# TMC2590_BOB40_V1_0.net
KiCad netlist of a schematic drawn in Altium Designer
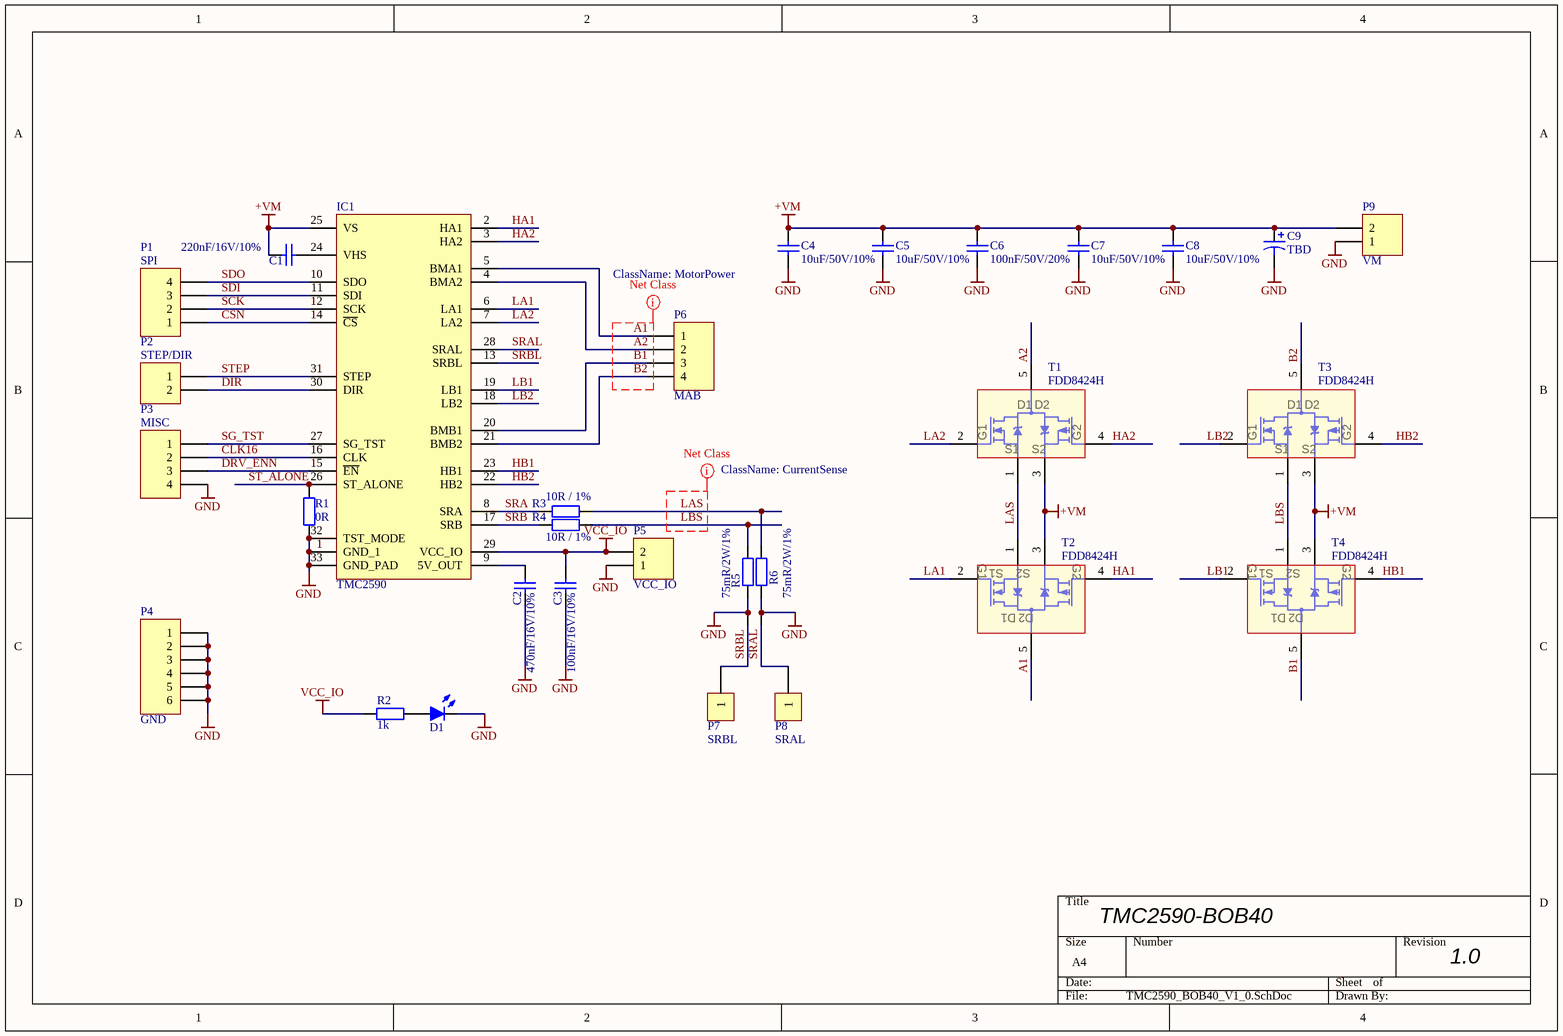
[diagram p0: TMC2590_BOB40_V1_0.SchDoc]

(export (version "E")
  (design (tool "Eeschema 10.0.6"))
  (components
    (comp (ref "C1")
      (value "220nF/16V/10%")
      (footprint "C0603")
      (description "Ceramic capacitor")
      (fields (field (name "MF") "Multicomp") (field (name "MPN") "MC0603B224K160CT"))
      (libsource (lib "SCH Passives") (part "Capacitor"))
    )
    (comp (ref "C2")
      (value "470nF/16V/10%")
      (footprint "C0603")
      (description "Ceramic capacitor")
      (fields (field (name "MF") "Multicomp") (field (name "MPN") "MC0603X474K160CT"))
      (libsource (lib "SCH Passives") (part "Capacitor"))
    )
    (comp (ref "C3")
      (value "100nF/16V/10%")
      (footprint "C0603")
      (description "Ceramic capacitor")
      (fields (field (name "MF") "Multicomp") (field (name "MPN") "MC0603B104K160CT"))
      (libsource (lib "SCH Passives") (part "Capacitor"))
    )
    (comp (ref "C4")
      (value "10uF/50V/10%")
      (footprint "C1206")
      (description "SMD Multilayer Ceramic Capacitor, 1206 [3216 Metric],10 µF, 50 V, ± 10%, X5R, GRM Series")
      (fields (field (name "MF") "MURATA") (field (name "MPN") "GRM31CR61H106KA12L"))
      (libsource (lib "TMC260_BOB_V1_1") (part "10 µF, 50 V, ± 10%, X5R, 1206 [3216 Metric]"))
    )
    (comp (ref "C5")
      (value "10uF/50V/10%")
      (footprint "C1206")
      (description "SMD Multilayer Ceramic Capacitor, 1206 [3216 Metric],10 µF, 50 V, ± 10%, X5R, GRM Series")
      (fields (field (name "MF") "MURATA") (field (name "MPN") "GRM31CR61H106KA12L"))
      (libsource (lib "TMC260_BOB_V1_1") (part "10 µF, 50 V, ± 10%, X5R, 1206 [3216 Metric]"))
    )
    (comp (ref "C6")
      (value "100nF/50V/20%")
      (footprint "C0603")
      (description "Ceramic capacitor")
      (fields (field (name "MF") "Multicomp") (field (name "MPN") "MC0603F104M500CT"))
      (libsource (lib "SCH Passives") (part "Capacitor"))
    )
    (comp (ref "C7")
      (value "10uF/50V/10%")
      (footprint "C1206")
      (description "SMD Multilayer Ceramic Capacitor, 1206 [3216 Metric],10 µF, 50 V, ± 10%, X5R, GRM Series")
      (fields (field (name "MF") "MURATA") (field (name "MPN") "GRM31CR61H106KA12L"))
      (libsource (lib "TMC260_BOB_V1_1") (part "10 µF, 50 V, ± 10%, X5R, 1206 [3216 Metric]"))
    )
    (comp (ref "C8")
      (value "10uF/50V/10%")
      (footprint "C1206")
      (description "SMD Multilayer Ceramic Capacitor, 1206 [3216 Metric],10 µF, 50 V, ± 10%, X5R, GRM Series")
      (fields (field (name "MF") "MURATA") (field (name "MPN") "GRM31CR61H106KA12L"))
      (libsource (lib "TMC260_BOB_V1_1") (part "10 µF, 50 V, ± 10%, X5R, 1206 [3216 Metric]"))
    )
    (comp (ref "C9")
      (value "TBD")
      (footprint "EXT_POL_CAP")
      (description "Polarized Capacitor (Radial)")
      (fields (field (name "Comment") "Cap Pol1") (field (name "PUBLISHER") "Altium Limited"))
      (libsource (lib "Miscellaneous Devices") (part "Cap Pol1"))
    )
    (comp (ref "D1")
      (value "LED, Blue, SMD, 20mA, 2.8V, 465 nm")
      (footprint "LED_0603")
      (fields (field (name "MF") "Lite-On") (field (name "MPN") "LTST-C191TBKT-5A"))
      (libsource (lib "TMC26x_RevA") (part "LED, Blue, SMD, 20mA, 2.8V, 465 nm"))
    )
    (comp (ref "IC1")
      (value "TMC2590")
      (footprint "TMC2590_QFP127P600-8N")
      (fields (field (name "MF") "TRINAMIC"))
      (libsource (lib "TMC2590_BOB40_V1_0") (part "TMC2590"))
    )
    (comp (ref "J1")
      (value "Net tie")
      (footprint "Net tie 10x20mil")
      (libsource (lib "TMC2590_BOB40_V1_0") (part "NET_TIE"))
    )
    (comp (ref "J2")
      (value "Net tie")
      (footprint "Net tie 10x20mil")
      (libsource (lib "TMC2590_BOB40_V1_0") (part "NET_TIE"))
    )
    (comp (ref "P1")
      (value "SPI")
      (footprint "4_PIN_THT")
      (description "Header, 4-Pin")
      (fields (field (name "PUBLISHER") "Altium Limited"))
      (libsource (lib "Miscellaneous Connectors") (part "Header 4"))
    )
    (comp (ref "P2")
      (value "STEP/DIR")
      (footprint "2_PIN_THT")
      (description "Header, 2-Pin")
      (fields (field (name "PUBLISHER") "Altium Limited"))
      (libsource (lib "") (part "Header 2_1"))
    )
    (comp (ref "P3")
      (value "MISC")
      (footprint "4_PIN_THT")
      (description "Header, 4-Pin")
      (fields (field (name "PUBLISHER") "Altium Limited"))
      (libsource (lib "") (part "Header 4_1"))
    )
    (comp (ref "P4")
      (value "GND")
      (footprint "6_PIN_THT")
      (description "Header, 6-Pin")
      (fields (field (name "PUBLISHER") "Altium Limited"))
      (libsource (lib "Miscellaneous Connectors") (part "Header 6"))
    )
    (comp (ref "P5")
      (value "VCC_IO")
      (footprint "2_PIN_THT")
      (description "Header, 2-Pin")
      (fields (field (name "PUBLISHER") "Altium Limited"))
      (libsource (lib "Miscellaneous Connectors") (part "Header 2"))
    )
    (comp (ref "P6")
      (value "MAB")
      (footprint "4_PIN_THT_1mm_hole")
      (description "Wire-To-Board Connector, 2.5 mm, 4 Contacts, Header, EH Series, Through Hole, 1 Rows")
      (fields (field (name "MPN") "B4B-EH-A") (field (name "MF") "JST (JAPAN SOLDERLESS TERMINALS)"))
      (libsource (lib "TMC5160_RevA") (part "Wire-To-Board Connector, 2.5 mm, 4 Contacts, Header, EH Series, Through Hole, 1 Rows"))
    )
    (comp (ref "P7")
      (value "SRBL")
      (footprint "TH_PIN - NO SILK")
      (libsource (lib "StepperMotorDriver_revA") (part "PIN"))
    )
    (comp (ref "P8")
      (value "SRAL")
      (footprint "TH_PIN - NO SILK")
      (libsource (lib "StepperMotorDriver_revA") (part "PIN"))
    )
    (comp (ref "P9")
      (value "VM")
      (footprint "2_PIN_THT")
      (description "Header, 2-Pin")
      (fields (field (name "PUBLISHER") "Altium Limited"))
      (libsource (lib "Miscellaneous Connectors") (part "Header 2"))
    )
    (comp (ref "R1")
      (value "0R")
      (footprint "R0603")
      (description "SMD Chip Resistor, Thick Film, 0 ohm, 0603 [1608 Metric], 100 mW, MCWR Series")
      (fields
        (field (name "MPN") "MCWR06X000 PTL")
        (field (name "MF") "MULTICOMP")
        (field (name "RESISTANCE") "0R")
      )
      (libsource (lib "SMD_Passives") (part "R, 0 ohm, 0603 [1608 Metric], 100 mW, MCWR Series"))
    )
    (comp (ref "R2")
      (value "1k")
      (footprint "R0603")
      (description "1 kohm, 50 V, 0603 [1608 Metric], 63 mW, ± 1%, MC Series")
      (fields
        (field (name "MPN") "MC0063W060311K")
        (field (name "MF") "MULTICOMP")
        (field (name "RESISTANCE") "1k")
      )
      (libsource (lib "TMC457_RevA") (part "1 kohm, 50 V, 0603 [1608 Metric], 63 mW, ± 1%, MC Series"))
    )
    (comp (ref "R3")
      (value "10R / 1%")
      (footprint "R0603")
      (description "SMD Chip Resistor, Thick Film, 10 ohm, 50 V, 0603 [1608 Metric], 100 mW, ± 1%, MCWR Series")
      (fields (field (name "MPN") "MCWR06X10R0FTL") (field (name "MF") "Multicomp"))
      (libsource (lib "TMC262_RevA") (part ".05 OHM 2W 1% Current Sense Resistor"))
    )
    (comp (ref "R4")
      (value "10R / 1%")
      (footprint "R0603")
      (description "SMD Chip Resistor, Thick Film, 10 ohm, 50 V, 0603 [1608 Metric], 100 mW, ± 1%, MCWR Series")
      (fields (field (name "MPN") "MCWR06X10R0FTL") (field (name "MF") "Multicomp"))
      (libsource (lib "TMC262_RevA") (part ".05 OHM 2W 1% Current Sense Resistor"))
    )
    (comp (ref "R5")
      (value "75mR/2W/1%")
      (footprint "R2512")
      (description "SMD Current Sense Resistor, 0.075 ohm, 2 W, 2512 [6432 Metric], ± 1%, TLR Series")
      (fields (field (name "MPN") "TLR3A20WR075FTDG") (field (name "MF") "TE CONNECTIVITY"))
      (libsource (lib "TMC262_RevA") (part ".075 OHM 2W 1% Current Sense Resistor"))
    )
    (comp (ref "R6")
      (value "75mR/2W/1%")
      (footprint "R2512")
      (description "SMD Current Sense Resistor, 0.075 ohm, 2 W, 2512 [6432 Metric], ± 1%, TLR Series")
      (fields (field (name "MPN") "TLR3A20WR075FTDG") (field (name "MF") "TE CONNECTIVITY"))
      (libsource (lib "TMC262_RevA") (part ".075 OHM 2W 1% Current Sense Resistor"))
    )
    (comp (ref "T1")
      (value "FDD8424H")
      (footprint "SOT114P991X239-6N")
      (description "Dual MOSFET, N and P Channel, 9 A, 40 V, 0.019 ohm, 10 V, 1.7 V")
      (fields (field (name "MF") "FAIRCHILD SEMICONDUCTOR"))
      (libsource (lib "") (part "FDD8424H_1"))
    )
    (comp (ref "T2")
      (value "FDD8424H")
      (footprint "SOT114P991X239-6N")
      (description "Dual MOSFET, N and P Channel, 9 A, 40 V, 0.019 ohm, 10 V, 1.7 V")
      (fields (field (name "MF") "FAIRCHILD SEMICONDUCTOR"))
      (libsource (lib "TMC262_FDD8424H_RevA") (part "FDD8424H"))
    )
    (comp (ref "T3")
      (value "FDD8424H")
      (footprint "SOT114P991X239-6N")
      (description "Dual MOSFET, N and P Channel, 9 A, 40 V, 0.019 ohm, 10 V, 1.7 V")
      (fields (field (name "MF") "FAIRCHILD SEMICONDUCTOR"))
      (libsource (lib "") (part "FDD8424H_1"))
    )
    (comp (ref "T4")
      (value "FDD8424H")
      (footprint "SOT114P991X239-6N")
      (description "Dual MOSFET, N and P Channel, 9 A, 40 V, 0.019 ohm, 10 V, 1.7 V")
      (fields (field (name "MF") "FAIRCHILD SEMICONDUCTOR"))
      (libsource (lib "TMC262_FDD8424H_RevA") (part "FDD8424H"))
    )
  )
  (nets
    (net (code "1") (name "+VM") (class "Default")
      (node (ref "C1") (pin "2") (pinfunction "2_2") (pintype "passive"))
      (node (ref "C4") (pin "2") (pinfunction "2_2") (pintype "passive"))
      (node (ref "C5") (pin "2") (pinfunction "2_2") (pintype "passive"))
      (node (ref "C6") (pin "2") (pinfunction "2_2") (pintype "passive"))
      (node (ref "C7") (pin "2") (pinfunction "2_2") (pintype "passive"))
      (node (ref "C8") (pin "2") (pinfunction "2_2") (pintype "passive"))
      (node (ref "C9") (pin "1") (pinfunction "1_1") (pintype "passive"))
      (node (ref "IC1") (pin "25") (pinfunction "VS_25") (pintype "power_in"))
      (node (ref "P9") (pin "2") (pinfunction "2_2") (pintype "passive"))
      (node (ref "T1") (pin "3") (pinfunction "S2_3") (pintype "passive"))
      (node (ref "T2") (pin "3") (pinfunction "S2_3") (pintype "passive"))
      (node (ref "T3") (pin "3") (pinfunction "S2_3") (pintype "passive"))
      (node (ref "T4") (pin "3") (pinfunction "S2_3") (pintype "passive"))
    )
    (net (code "2") (name "/A1") (class "Default")
      (node (ref "IC1") (pin "5") (pinfunction "BMA1_5") (pintype "passive"))
      (node (ref "P6") (pin "1") (pinfunction "1_1") (pintype "passive"))
      (node (ref "T2") (pin "5") (pinfunction "D1/D2_5") (pintype "passive"))
    )
    (net (code "3") (name "/A2") (class "Default")
      (node (ref "IC1") (pin "4") (pinfunction "BMA2_4") (pintype "passive"))
      (node (ref "P6") (pin "2") (pinfunction "2_2") (pintype "passive"))
      (node (ref "T1") (pin "5") (pinfunction "D1/D2_5") (pintype "passive"))
    )
    (net (code "4") (name "/B1") (class "Default")
      (node (ref "IC1") (pin "20") (pinfunction "BMB1_20") (pintype "passive"))
      (node (ref "P6") (pin "3") (pinfunction "3_3") (pintype "passive"))
      (node (ref "T4") (pin "5") (pinfunction "D1/D2_5") (pintype "passive"))
    )
    (net (code "5") (name "/B2") (class "Default")
      (node (ref "IC1") (pin "21") (pinfunction "BMB2_21") (pintype "passive"))
      (node (ref "P6") (pin "4") (pinfunction "4_4") (pintype "passive"))
      (node (ref "T3") (pin "5") (pinfunction "D1/D2_5") (pintype "passive"))
    )
    (net (code "6") (name "/CLK16") (class "Default")
      (node (ref "IC1") (pin "16") (pinfunction "CLK_16") (pintype "passive"))
      (node (ref "P3") (pin "2") (pinfunction "2_2") (pintype "passive"))
    )
    (net (code "7") (name "/CSN") (class "Default")
      (node (ref "IC1") (pin "14") (pinfunction "~{CS}_14") (pintype "passive"))
      (node (ref "P1") (pin "1") (pinfunction "1_1") (pintype "passive"))
    )
    (net (code "8") (name "/DIR") (class "Default")
      (node (ref "IC1") (pin "30") (pinfunction "DIR_30") (pintype "passive"))
      (node (ref "P2") (pin "2") (pinfunction "2_2") (pintype "passive"))
    )
    (net (code "9") (name "/DRV_ENN") (class "Default")
      (node (ref "IC1") (pin "15") (pinfunction "~{EN}_15") (pintype "passive"))
      (node (ref "P3") (pin "3") (pinfunction "3_3") (pintype "passive"))
    )
    (net (code "10") (name "/HA1") (class "Default")
      (node (ref "IC1") (pin "2") (pinfunction "HA1_2") (pintype "passive"))
      (node (ref "T2") (pin "4") (pinfunction "G2_4") (pintype "passive"))
    )
    (net (code "11") (name "/HA2") (class "Default")
      (node (ref "IC1") (pin "3") (pinfunction "HA2_3") (pintype "passive"))
      (node (ref "T1") (pin "4") (pinfunction "G2_4") (pintype "passive"))
    )
    (net (code "12") (name "/HB1") (class "Default")
      (node (ref "IC1") (pin "23") (pinfunction "HB1_23") (pintype "passive"))
      (node (ref "T4") (pin "4") (pinfunction "G2_4") (pintype "passive"))
    )
    (net (code "13") (name "/HB2") (class "Default")
      (node (ref "IC1") (pin "22") (pinfunction "HB2_22") (pintype "passive"))
      (node (ref "T3") (pin "4") (pinfunction "G2_4") (pintype "passive"))
    )
    (net (code "14") (name "/LA1") (class "Default")
      (node (ref "IC1") (pin "6") (pinfunction "LA1_6") (pintype "passive"))
      (node (ref "T2") (pin "2") (pinfunction "G1_2") (pintype "passive"))
    )
    (net (code "15") (name "/LA2") (class "Default")
      (node (ref "IC1") (pin "7") (pinfunction "LA2_7") (pintype "passive"))
      (node (ref "T1") (pin "2") (pinfunction "G1_2") (pintype "passive"))
    )
    (net (code "16") (name "/LAS") (class "Default")
      (node (ref "R3") (pin "1") (pinfunction "1_1") (pintype "passive"))
      (node (ref "R6") (pin "2") (pinfunction "2_2") (pintype "passive"))
      (node (ref "T1") (pin "1") (pinfunction "S1_1") (pintype "passive"))
      (node (ref "T2") (pin "1") (pinfunction "S1_1") (pintype "passive"))
    )
    (net (code "17") (name "/LB1") (class "Default")
      (node (ref "IC1") (pin "19") (pinfunction "LB1_19") (pintype "passive"))
      (node (ref "T4") (pin "2") (pinfunction "G1_2") (pintype "passive"))
    )
    (net (code "18") (name "/LB2") (class "Default")
      (node (ref "IC1") (pin "18") (pinfunction "LB2_18") (pintype "passive"))
      (node (ref "T3") (pin "2") (pinfunction "G1_2") (pintype "passive"))
    )
    (net (code "19") (name "/LBS") (class "Default")
      (node (ref "R4") (pin "1") (pinfunction "1_1") (pintype "passive"))
      (node (ref "R5") (pin "2") (pinfunction "2_2") (pintype "passive"))
      (node (ref "T3") (pin "1") (pinfunction "S1_1") (pintype "passive"))
      (node (ref "T4") (pin "1") (pinfunction "S1_1") (pintype "passive"))
    )
    (net (code "20") (name "/SCK") (class "Default")
      (node (ref "IC1") (pin "12") (pinfunction "SCK_12") (pintype "passive"))
      (node (ref "P1") (pin "2") (pinfunction "2_2") (pintype "passive"))
    )
    (net (code "21") (name "/SDI") (class "Default")
      (node (ref "IC1") (pin "11") (pinfunction "SDI_11") (pintype "passive"))
      (node (ref "P1") (pin "3") (pinfunction "3_3") (pintype "passive"))
    )
    (net (code "22") (name "/SDO") (class "Default")
      (node (ref "IC1") (pin "10") (pinfunction "SDO_10") (pintype "passive"))
      (node (ref "P1") (pin "4") (pinfunction "4_4") (pintype "passive"))
    )
    (net (code "23") (name "/SG_TST") (class "Default")
      (node (ref "IC1") (pin "27") (pinfunction "SG_TST_27") (pintype "passive"))
      (node (ref "P3") (pin "1") (pinfunction "1_1") (pintype "passive"))
    )
    (net (code "24") (name "/SRA") (class "Default")
      (node (ref "IC1") (pin "8") (pinfunction "SRA_8") (pintype "passive"))
      (node (ref "R3") (pin "2") (pinfunction "2_2") (pintype "passive"))
    )
    (net (code "25") (name "/SRAL") (class "Default")
      (node (ref "IC1") (pin "28") (pinfunction "SRAL_28") (pintype "passive"))
      (node (ref "J2") (pin "1") (pinfunction "1_1") (pintype "passive"))
      (node (ref "P8") (pin "1") (pinfunction "1_1") (pintype "passive"))
    )
    (net (code "26") (name "/SRB") (class "Default")
      (node (ref "IC1") (pin "17") (pinfunction "SRB_17") (pintype "passive"))
      (node (ref "R4") (pin "2") (pinfunction "2_2") (pintype "passive"))
    )
    (net (code "27") (name "/SRBL") (class "Default")
      (node (ref "IC1") (pin "13") (pinfunction "SRBL_13") (pintype "passive"))
      (node (ref "J1") (pin "1") (pinfunction "1_1") (pintype "passive"))
      (node (ref "P7") (pin "1") (pinfunction "1_1") (pintype "passive"))
    )
    (net (code "28") (name "/STEP") (class "Default")
      (node (ref "IC1") (pin "31") (pinfunction "STEP_31") (pintype "passive"))
      (node (ref "P2") (pin "1") (pinfunction "1_1") (pintype "passive"))
    )
    (net (code "29") (name "/ST_ALONE") (class "Default")
      (node (ref "IC1") (pin "26") (pinfunction "ST_ALONE_26") (pintype "passive"))
      (node (ref "R1") (pin "1") (pinfunction "1_1") (pintype "passive"))
    )
    (net (code "30") (name "GND") (class "Default")
      (node (ref "C2") (pin "2") (pinfunction "2_2") (pintype "passive"))
      (node (ref "C3") (pin "2") (pinfunction "2_2") (pintype "passive"))
      (node (ref "C4") (pin "1") (pinfunction "1_1") (pintype "passive"))
      (node (ref "C5") (pin "1") (pinfunction "1_1") (pintype "passive"))
      (node (ref "C6") (pin "1") (pinfunction "1_1") (pintype "passive"))
      (node (ref "C7") (pin "1") (pinfunction "1_1") (pintype "passive"))
      (node (ref "C8") (pin "1") (pinfunction "1_1") (pintype "passive"))
      (node (ref "C9") (pin "2") (pinfunction "2_2") (pintype "passive"))
      (node (ref "D1") (pin "2") (pinfunction "K_2") (pintype "passive"))
      (node (ref "IC1") (pin "1") (pinfunction "GND_1_1") (pintype "passive"))
      (node (ref "IC1") (pin "32") (pinfunction "TST_MODE_32") (pintype "passive"))
      (node (ref "IC1") (pin "33") (pinfunction "GND_PAD_33") (pintype "passive"))
      (node (ref "J1") (pin "2") (pinfunction "2_2") (pintype "passive"))
      (node (ref "J2") (pin "2") (pinfunction "2_2") (pintype "passive"))
      (node (ref "P3") (pin "4") (pinfunction "4_4") (pintype "passive"))
      (node (ref "P4") (pin "1") (pinfunction "1_1") (pintype "passive"))
      (node (ref "P4") (pin "2") (pinfunction "2_2") (pintype "passive"))
      (node (ref "P4") (pin "3") (pinfunction "3_3") (pintype "passive"))
      (node (ref "P4") (pin "4") (pinfunction "4_4") (pintype "passive"))
      (node (ref "P4") (pin "5") (pinfunction "5_5") (pintype "passive"))
      (node (ref "P4") (pin "6") (pinfunction "6_6") (pintype "passive"))
      (node (ref "P5") (pin "1") (pinfunction "1_1") (pintype "passive"))
      (node (ref "P9") (pin "1") (pinfunction "1_1") (pintype "passive"))
      (node (ref "R1") (pin "2") (pinfunction "2_2") (pintype "passive"))
      (node (ref "R5") (pin "1") (pinfunction "1_1") (pintype "passive"))
      (node (ref "R6") (pin "1") (pinfunction "1_1") (pintype "passive"))
    )
    (net (code "31") (name "Net-(D1-A)") (class "Default")
      (node (ref "D1") (pin "1") (pinfunction "A_1") (pintype "passive"))
      (node (ref "R2") (pin "2") (pinfunction "2_2") (pintype "passive"))
    )
    (net (code "32") (name "Net-(IC1-5V_OUT)") (class "Default")
      (node (ref "C2") (pin "1") (pinfunction "1_1") (pintype "passive"))
      (node (ref "IC1") (pin "9") (pinfunction "5V_OUT_9") (pintype "power_in"))
    )
    (net (code "33") (name "Net-(IC1-VHS)") (class "Default")
      (node (ref "C1") (pin "1") (pinfunction "1_1") (pintype "passive"))
      (node (ref "IC1") (pin "24") (pinfunction "VHS_24") (pintype "power_in"))
    )
    (net (code "34") (name "VCC_IO") (class "Default")
      (node (ref "C3") (pin "1") (pinfunction "1_1") (pintype "passive"))
      (node (ref "IC1") (pin "29") (pinfunction "VCC_IO_29") (pintype "power_in"))
      (node (ref "P5") (pin "2") (pinfunction "2_2") (pintype "passive"))
      (node (ref "R2") (pin "1") (pinfunction "1_1") (pintype "passive"))
    )
  )
)
